# JTAG_Configuration.net
KiCad netlist of a schematic drawn in Altium Designer
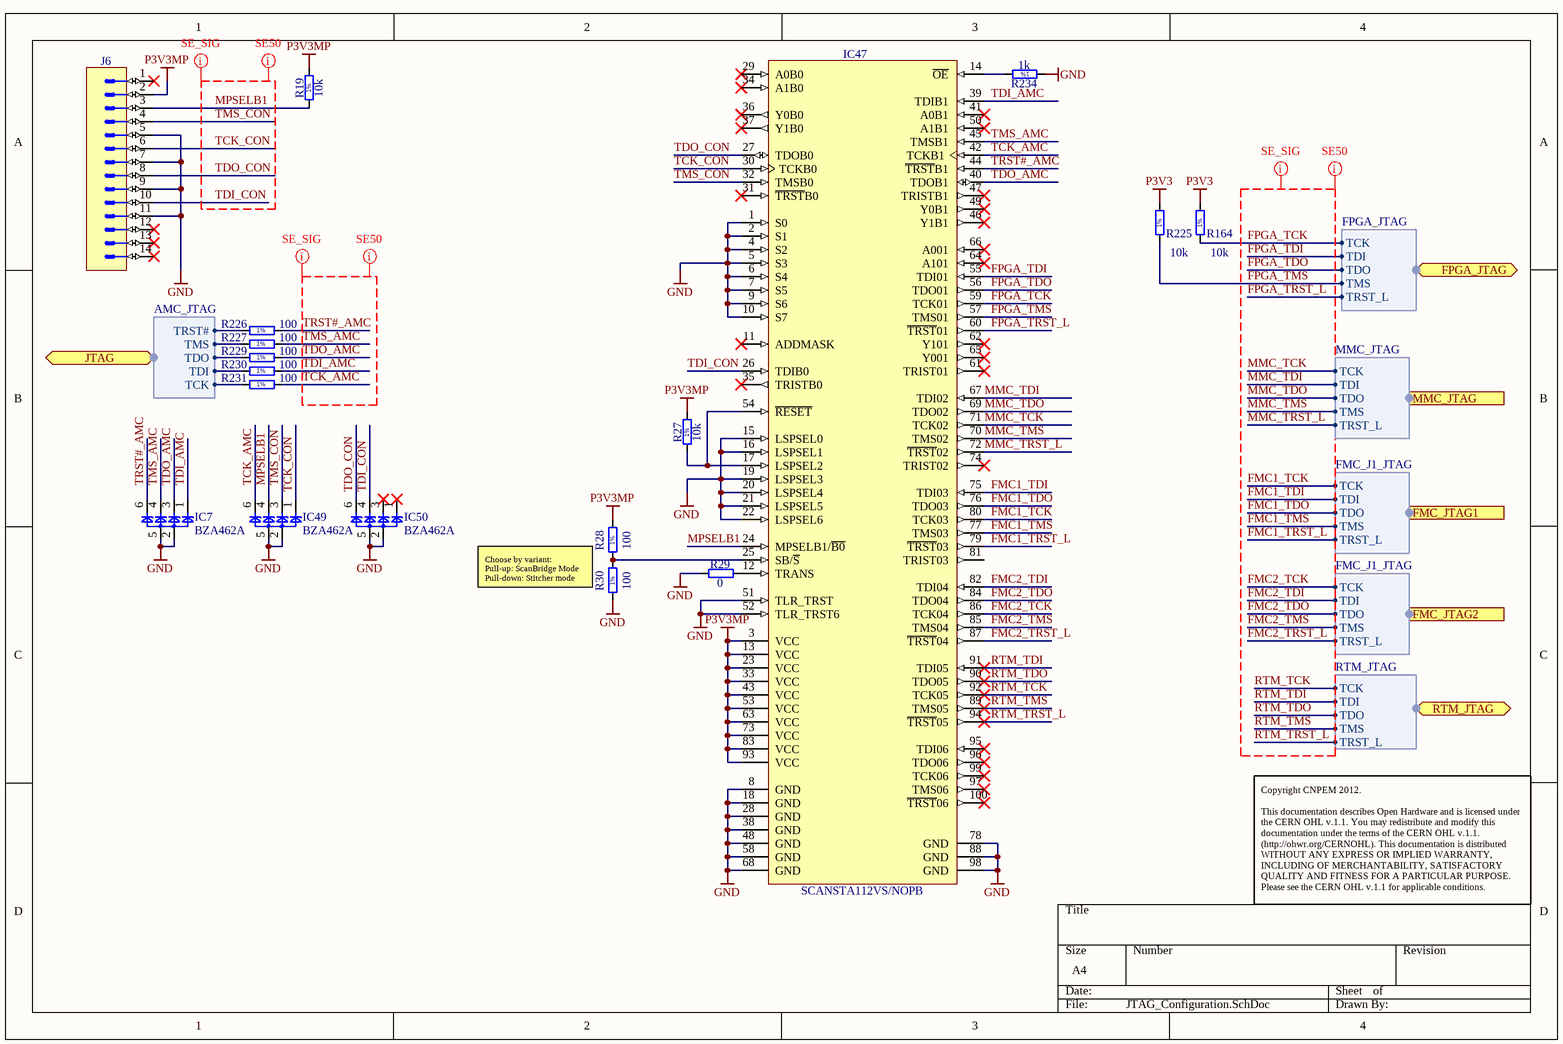
[diagram p0: JTAG_Configuration.SchDoc]

(export (version "E")
  (design (tool "Eeschema 10.0.6"))
  (components
    (comp (ref "IC7")
      (value "BZA462A")
      (footprint "SOT23-6")
      (description "Quadruple 4V ESD transient voltage suppressor")
      (libsource (lib "LIBRARY_SCH") (part "D_TVS_BZA462A"))
    )
    (comp (ref "IC47")
      (value "SCANSTA112VS/NOPB")
      (footprint "QFP50P1600X1600X120-100N")
      (description "7-Port Multidrop IEEE 1149.1 (JTAG) Multiplexer")
      (fields (field (name "MANUFACTURER") "TEXAS INSTRUMENTS") (field (name "AUTHOR") "CERN DEM JLC"))
      (libsource (lib "ICs And Semiconductors") (part "SCANSTA112VS"))
    )
    (comp (ref "IC49")
      (value "BZA462A")
      (footprint "SOT23-6")
      (description "Quadruple 4V ESD transient voltage suppressor")
      (libsource (lib "LIBRARY_SCH") (part "D_TVS_BZA462A"))
    )
    (comp (ref "IC50")
      (value "BZA462A")
      (footprint "SOT23-6")
      (description "Quadruple 4V ESD transient voltage suppressor")
      (libsource (lib "LIBRARY_SCH") (part "D_TVS_BZA462A"))
    )
    (comp (ref "J6")
      (value "Milli-Grid™")
      (footprint "MOLEX_87832-1420")
      (description "Connector 14 Male")
      (fields
        (field (name "PART NUMBER") "MOLEX_87832-1420")
        (field (name "MANUFACTURER") "MOLEX")
        (field (name "AUTHOR") "CERN DEM JLC")
      )
      (libsource (lib "Connectors") (part "Connector 14 Male"))
    )
    (comp (ref "R19")
      (value "10k")
      (footprint "RESC1608X55N")
      (description "Resistor - 1%")
      (fields
        (field (name "PART NUMBER") "R0603_10K_1%_0.1W_100PPM")
        (field (name "POWER") "0.1W")
        (field (name "AUTHOR") "CERN DEM JLC")
      )
      (libsource (lib "Resistors") (part "Resistor - 1%"))
    )
    (comp (ref "R27")
      (value "10k")
      (footprint "RESC1608X55N")
      (description "Resistor - 1%")
      (fields
        (field (name "PART NUMBER") "R0603_10K_1%_0.1W_100PPM")
        (field (name "POWER") "0.1W")
        (field (name "AUTHOR") "CERN DEM JLC")
      )
      (libsource (lib "Resistors") (part "Resistor - 1%"))
    )
    (comp (ref "R28")
      (value "100")
      (footprint "RESC1005X40N")
      (description "Resistor - 1%")
      (fields
        (field (name "PART NUMBER") "R0402_100R_1%_0.0625W_100PPM")
        (field (name "POWER") "0.0625W")
        (field (name "AUTHOR") "CERN DEM JLC")
      )
      (libsource (lib "Resistors") (part "Resistor - 1%"))
    )
    (comp (ref "R29")
      (value "0")
      (footprint "RESC1608X55N")
      (description "Resistor")
      (fields
        (field (name "PART NUMBER") "R0603_0R_JUMPER")
        (field (name "MANUFACTURER") "GENERIC")
        (field (name "AUTHOR") "CERN DEM JLC")
      )
      (libsource (lib "Resistors") (part "Resistor"))
    )
    (comp (ref "R30")
      (value "100")
      (footprint "RESC1005X40N")
      (description "Resistor - 1%")
      (fields
        (field (name "PART NUMBER") "R0402_100R_1%_0.0625W_100PPM")
        (field (name "POWER") "0.0625W")
        (field (name "AUTHOR") "CERN DEM JLC")
      )
      (libsource (lib "Resistors") (part "Resistor - 1%"))
    )
    (comp (ref "R164")
      (value "10k")
      (footprint "RESC1005X40N")
      (description "Resistor - 1%")
      (fields
        (field (name "PART NUMBER") "R0402_10K_1%_0.0625W_100PPM")
        (field (name "POWER") "0.0625W")
        (field (name "AUTHOR") "CERN DEM JLC")
      )
      (libsource (lib "Resistors") (part "Resistor - 1%"))
    )
    (comp (ref "R225")
      (value "10k")
      (footprint "RESC1005X40N")
      (description "Resistor - 1%")
      (fields
        (field (name "PART NUMBER") "R0402_10K_1%_0.0625W_100PPM")
        (field (name "POWER") "0.0625W")
        (field (name "AUTHOR") "CERN DEM JLC")
      )
      (libsource (lib "Resistors") (part "Resistor - 1%"))
    )
    (comp (ref "R226")
      (value "100")
      (footprint "RESC1005X40N")
      (description "Resistor - 1%")
      (fields
        (field (name "PART NUMBER") "R0402_100R_1%_0.0625W_100PPM")
        (field (name "POWER") "0.0625W")
        (field (name "AUTHOR") "CERN DEM JLC")
      )
      (libsource (lib "Resistors") (part "Resistor - 1%"))
    )
    (comp (ref "R227")
      (value "100")
      (footprint "RESC1005X40N")
      (description "Resistor - 1%")
      (fields
        (field (name "PART NUMBER") "R0402_100R_1%_0.0625W_100PPM")
        (field (name "POWER") "0.0625W")
        (field (name "AUTHOR") "CERN DEM JLC")
      )
      (libsource (lib "Resistors") (part "Resistor - 1%"))
    )
    (comp (ref "R229")
      (value "100")
      (footprint "RESC1005X40N")
      (description "Resistor - 1%")
      (fields
        (field (name "PART NUMBER") "R0402_100R_1%_0.0625W_100PPM")
        (field (name "POWER") "0.0625W")
        (field (name "AUTHOR") "CERN DEM JLC")
      )
      (libsource (lib "Resistors") (part "Resistor - 1%"))
    )
    (comp (ref "R230")
      (value "100")
      (footprint "RESC1005X40N")
      (description "Resistor - 1%")
      (fields
        (field (name "PART NUMBER") "R0402_100R_1%_0.0625W_100PPM")
        (field (name "POWER") "0.0625W")
        (field (name "AUTHOR") "CERN DEM JLC")
      )
      (libsource (lib "Resistors") (part "Resistor - 1%"))
    )
    (comp (ref "R231")
      (value "100")
      (footprint "RESC1005X40N")
      (description "Resistor - 1%")
      (fields
        (field (name "PART NUMBER") "R0402_100R_1%_0.0625W_100PPM")
        (field (name "POWER") "0.0625W")
        (field (name "AUTHOR") "CERN DEM JLC")
      )
      (libsource (lib "Resistors") (part "Resistor - 1%"))
    )
    (comp (ref "R234")
      (value "1k")
      (footprint "RESC1005X40N")
      (description "Resistor - 1%")
      (fields
        (field (name "PART NUMBER") "R0402_1K_1%_0.0625W_100PPM")
        (field (name "POWER") "0.0625W")
        (field (name "AUTHOR") "CERN DEM JLC")
      )
      (libsource (lib "Resistors") (part "Resistor - 1%"))
    )
  )
  (nets
    (net (code "6") (name "/FMC1_TCK") (class "Default")
      (node (ref "IC47") (pin "80") (pinfunction "TCK03_80") (pintype "output"))
    )
    (net (code "7") (name "/FMC1_TDI") (class "Default")
      (node (ref "IC47") (pin "75") (pinfunction "TDI03_75") (pintype "input"))
    )
    (net (code "8") (name "/FMC1_TDO") (class "Default")
      (node (ref "IC47") (pin "76") (pinfunction "TDO03_76") (pintype "output"))
    )
    (net (code "9") (name "/FMC1_TMS") (class "Default")
      (node (ref "IC47") (pin "77") (pinfunction "TMS03_77") (pintype "output"))
    )
    (net (code "10") (name "/FMC1_TRST_L") (class "Default")
      (node (ref "IC47") (pin "79") (pinfunction "~{TRST}03_79") (pintype "output"))
    )
    (net (code "11") (name "/FMC2_TCK") (class "Default")
      (node (ref "IC47") (pin "86") (pinfunction "TCK04_86") (pintype "output"))
    )
    (net (code "12") (name "/FMC2_TDI") (class "Default")
      (node (ref "IC47") (pin "82") (pinfunction "TDI04_82") (pintype "input"))
    )
    (net (code "13") (name "/FMC2_TDO") (class "Default")
      (node (ref "IC47") (pin "84") (pinfunction "TDO04_84") (pintype "output"))
    )
    (net (code "14") (name "/FMC2_TMS") (class "Default")
      (node (ref "IC47") (pin "85") (pinfunction "TMS04_85") (pintype "output"))
    )
    (net (code "15") (name "/FMC2_TRST_L") (class "Default")
      (node (ref "IC47") (pin "87") (pinfunction "~{TRST}04_87") (pintype "output"))
    )
    (net (code "16") (name "/FPGA_TCK") (class "Default")
      (node (ref "IC47") (pin "59") (pinfunction "TCK01_59") (pintype "output"))
      (node (ref "R164") (pin "1") (pinfunction "1_1") (pintype "passive"))
    )
    (net (code "17") (name "/FPGA_TDI") (class "Default")
      (node (ref "IC47") (pin "55") (pinfunction "TDI01_55") (pintype "input"))
    )
    (net (code "18") (name "/FPGA_TDO") (class "Default")
      (node (ref "IC47") (pin "56") (pinfunction "TDO01_56") (pintype "output"))
    )
    (net (code "19") (name "/FPGA_TMS") (class "Default")
      (node (ref "IC47") (pin "57") (pinfunction "TMS01_57") (pintype "output"))
      (node (ref "R225") (pin "1") (pinfunction "1_1") (pintype "passive"))
    )
    (net (code "20") (name "/FPGA_TRST_L") (class "Default")
      (node (ref "IC47") (pin "60") (pinfunction "~{TRST}01_60") (pintype "output"))
    )
    (net (code "21") (name "/MMC_TCK") (class "Default")
      (node (ref "IC47") (pin "71") (pinfunction "TCK02_71") (pintype "output"))
    )
    (net (code "22") (name "/MMC_TDI") (class "Default")
      (node (ref "IC47") (pin "67") (pinfunction "TDI02_67") (pintype "input"))
    )
    (net (code "23") (name "/MMC_TDO") (class "Default")
      (node (ref "IC47") (pin "69") (pinfunction "TDO02_69") (pintype "output"))
    )
    (net (code "24") (name "/MMC_TMS") (class "Default")
      (node (ref "IC47") (pin "70") (pinfunction "TMS02_70") (pintype "output"))
    )
    (net (code "25") (name "/MMC_TRST_L") (class "Default")
      (node (ref "IC47") (pin "72") (pinfunction "~{TRST}02_72") (pintype "output"))
    )
    (net (code "26") (name "/MPSELB1") (class "Default")
      (node (ref "IC47") (pin "24") (pinfunction "MPSELB1/~{B0}_24") (pintype "input"))
      (node (ref "IC49") (pin "4") (pinfunction "4_4") (pintype "passive"))
      (node (ref "J6") (pin "3") (pinfunction "3_3") (pintype "bidirectional"))
      (node (ref "R19") (pin "1") (pinfunction "1_1") (pintype "passive"))
    )
    (net (code "27") (name "/RTM_TCK") (class "Default")
      (node (ref "IC47") (pin "92") (pinfunction "TCK05_92") (pintype "output+no_connect"))
    )
    (net (code "28") (name "/RTM_TDI") (class "Default")
      (node (ref "IC47") (pin "91") (pinfunction "TDI05_91") (pintype "input"))
    )
    (net (code "29") (name "/RTM_TDO") (class "Default")
      (node (ref "IC47") (pin "90") (pinfunction "TDO05_90") (pintype "output"))
    )
    (net (code "30") (name "/RTM_TMS") (class "Default")
      (node (ref "IC47") (pin "89") (pinfunction "TMS05_89") (pintype "output"))
    )
    (net (code "31") (name "/RTM_TRST_L") (class "Default")
      (node (ref "IC47") (pin "94") (pinfunction "~{TRST}05_94") (pintype "output+no_connect"))
    )
    (net (code "32") (name "/TCK_AMC") (class "Default")
      (node (ref "IC47") (pin "42") (pinfunction "TCKB1_42") (pintype "input"))
      (node (ref "IC49") (pin "6") (pinfunction "6_6") (pintype "passive"))
      (node (ref "R231") (pin "2") (pinfunction "2_2") (pintype "passive"))
    )
    (net (code "33") (name "/TCK_CON") (class "Default")
      (node (ref "IC47") (pin "30") (pinfunction "TCKB0_30") (pintype "input"))
      (node (ref "IC49") (pin "1") (pinfunction "1_1") (pintype "passive"))
      (node (ref "J6") (pin "6") (pinfunction "6_6") (pintype "bidirectional"))
    )
    (net (code "34") (name "/TDI_AMC") (class "Default")
      (node (ref "IC47") (pin "39") (pinfunction "TDIB1_39") (pintype "input"))
      (node (ref "IC7") (pin "1") (pinfunction "1_1") (pintype "passive"))
      (node (ref "R230") (pin "2") (pinfunction "2_2") (pintype "passive"))
    )
    (net (code "35") (name "/TDI_CON") (class "Default")
      (node (ref "IC47") (pin "26") (pinfunction "TDIB0_26") (pintype "input"))
      (node (ref "IC50") (pin "4") (pinfunction "4_4") (pintype "passive"))
      (node (ref "J6") (pin "10") (pinfunction "10_10") (pintype "bidirectional"))
    )
    (net (code "36") (name "/TDO_AMC") (class "Default")
      (node (ref "IC47") (pin "40") (pinfunction "TDOB1_40") (pintype "bidirectional"))
      (node (ref "IC7") (pin "3") (pinfunction "3_3") (pintype "passive"))
      (node (ref "R229") (pin "2") (pinfunction "2_2") (pintype "passive"))
    )
    (net (code "37") (name "/TDO_CON") (class "Default")
      (node (ref "IC47") (pin "27") (pinfunction "TDOB0_27") (pintype "bidirectional"))
      (node (ref "IC50") (pin "6") (pinfunction "6_6") (pintype "passive"))
      (node (ref "J6") (pin "8") (pinfunction "8_8") (pintype "bidirectional"))
    )
    (net (code "38") (name "/TMS_AMC") (class "Default")
      (node (ref "IC47") (pin "45") (pinfunction "TMSB1_45") (pintype "input"))
      (node (ref "IC7") (pin "4") (pinfunction "4_4") (pintype "passive"))
      (node (ref "R227") (pin "2") (pinfunction "2_2") (pintype "passive"))
    )
    (net (code "39") (name "/TMS_CON") (class "Default")
      (node (ref "IC47") (pin "32") (pinfunction "TMSB0_32") (pintype "input"))
      (node (ref "IC49") (pin "3") (pinfunction "3_3") (pintype "passive"))
      (node (ref "J6") (pin "4") (pinfunction "4_4") (pintype "bidirectional"))
    )
    (net (code "40") (name "/TRST#") (class "Default")
      (node (ref "R226") (pin "1") (pinfunction "1_1") (pintype "passive"))
    )
    (net (code "41") (name "/TRST#_AMC") (class "Default")
      (node (ref "IC47") (pin "44") (pinfunction "~{TRST}B1_44") (pintype "input"))
      (node (ref "IC7") (pin "6") (pinfunction "6_6") (pintype "passive"))
      (node (ref "R226") (pin "2") (pinfunction "2_2") (pintype "passive"))
    )
    (net (code "47") (name "GND") (class "Default")
      (node (ref "IC47") (pin "1") (pinfunction "S0_1") (pintype "input"))
      (node (ref "IC47") (pin "10") (pinfunction "S7_10") (pintype "input"))
      (node (ref "IC47") (pin "15") (pinfunction "LSPSEL0_15") (pintype "input"))
      (node (ref "IC47") (pin "16") (pinfunction "LSPSEL1_16") (pintype "input"))
      (node (ref "IC47") (pin "18") (pinfunction "GND_18") (pintype "power_in"))
      (node (ref "IC47") (pin "19") (pinfunction "LSPSEL3_19") (pintype "input"))
      (node (ref "IC47") (pin "2") (pinfunction "S1_2") (pintype "input"))
      (node (ref "IC47") (pin "20") (pinfunction "LSPSEL4_20") (pintype "input"))
      (node (ref "IC47") (pin "21") (pinfunction "LSPSEL5_21") (pintype "input"))
      (node (ref "IC47") (pin "22") (pinfunction "LSPSEL6_22") (pintype "input"))
      (node (ref "IC47") (pin "28") (pinfunction "GND_28") (pintype "power_in"))
      (node (ref "IC47") (pin "38") (pinfunction "GND_38") (pintype "power_in"))
      (node (ref "IC47") (pin "4") (pinfunction "S2_4") (pintype "input"))
      (node (ref "IC47") (pin "48") (pinfunction "GND_48") (pintype "power_in"))
      (node (ref "IC47") (pin "5") (pinfunction "S3_5") (pintype "input"))
      (node (ref "IC47") (pin "51") (pinfunction "TLR_TRST_51") (pintype "input"))
      (node (ref "IC47") (pin "52") (pinfunction "TLR_TRST6_52") (pintype "input"))
      (node (ref "IC47") (pin "58") (pinfunction "GND_58") (pintype "power_in"))
      (node (ref "IC47") (pin "6") (pinfunction "S4_6") (pintype "input"))
      (node (ref "IC47") (pin "68") (pinfunction "GND_68") (pintype "power_in"))
      (node (ref "IC47") (pin "7") (pinfunction "S5_7") (pintype "input"))
      (node (ref "IC47") (pin "78") (pinfunction "GND_78") (pintype "power_in"))
      (node (ref "IC47") (pin "8") (pinfunction "GND_8") (pintype "power_in"))
      (node (ref "IC47") (pin "88") (pinfunction "GND_88") (pintype "power_in"))
      (node (ref "IC47") (pin "9") (pinfunction "S6_9") (pintype "input"))
      (node (ref "IC47") (pin "98") (pinfunction "GND_98") (pintype "power_in"))
      (node (ref "IC49") (pin "2") (pinfunction "2_2") (pintype "passive"))
      (node (ref "IC49") (pin "5") (pinfunction "5_5") (pintype "passive"))
      (node (ref "IC50") (pin "2") (pinfunction "2_2") (pintype "passive"))
      (node (ref "IC50") (pin "5") (pinfunction "5_5") (pintype "passive"))
      (node (ref "IC7") (pin "2") (pinfunction "2_2") (pintype "passive"))
      (node (ref "IC7") (pin "5") (pinfunction "5_5") (pintype "passive"))
      (node (ref "J6") (pin "11") (pinfunction "11_11") (pintype "bidirectional"))
      (node (ref "J6") (pin "5") (pinfunction "5_5") (pintype "bidirectional"))
      (node (ref "J6") (pin "7") (pinfunction "7_7") (pintype "bidirectional"))
      (node (ref "J6") (pin "9") (pinfunction "9_9") (pintype "bidirectional"))
      (node (ref "R234") (pin "1") (pinfunction "1_1") (pintype "passive"))
      (node (ref "R29") (pin "1") (pinfunction "1_1") (pintype "passive"))
      (node (ref "R30") (pin "1") (pinfunction "1_1") (pintype "passive"))
    )
    (net (code "48") (name "Net-(IC47-LSPSEL2)") (class "Default")
      (node (ref "IC47") (pin "17") (pinfunction "LSPSEL2_17") (pintype "input"))
      (node (ref "IC47") (pin "54") (pinfunction "~{RESET}_54") (pintype "input"))
      (node (ref "R27") (pin "1") (pinfunction "1_1") (pintype "passive"))
    )
    (net (code "49") (name "Net-(IC47-SB{slash}~{S})") (class "Default")
      (node (ref "IC47") (pin "25") (pinfunction "SB/~{S}_25") (pintype "input"))
      (node (ref "R28") (pin "1") (pinfunction "1_1") (pintype "passive"))
      (node (ref "R30") (pin "2") (pinfunction "2_2") (pintype "passive"))
    )
    (net (code "50") (name "Net-(IC47-TRANS)") (class "Default")
      (node (ref "IC47") (pin "12") (pinfunction "TRANS_12") (pintype "input"))
      (node (ref "R29") (pin "2") (pinfunction "2_2") (pintype "passive"))
    )
    (net (code "51") (name "Net-(IC47-~{OE})") (class "Default")
      (node (ref "IC47") (pin "14") (pinfunction "~{OE}_14") (pintype "input"))
      (node (ref "R234") (pin "2") (pinfunction "2_2") (pintype "passive"))
    )
    (net (code "52") (name "P3V3") (class "Default")
      (node (ref "R164") (pin "2") (pinfunction "2_2") (pintype "passive"))
      (node (ref "R225") (pin "2") (pinfunction "2_2") (pintype "passive"))
    )
    (net (code "53") (name "P3V3MP") (class "Default")
      (node (ref "IC47") (pin "13") (pinfunction "VCC_13") (pintype "power_in"))
      (node (ref "IC47") (pin "23") (pinfunction "VCC_23") (pintype "power_in"))
      (node (ref "IC47") (pin "3") (pinfunction "VCC_3") (pintype "power_in"))
      (node (ref "IC47") (pin "33") (pinfunction "VCC_33") (pintype "power_in"))
      (node (ref "IC47") (pin "43") (pinfunction "VCC_43") (pintype "power_in"))
      (node (ref "IC47") (pin "53") (pinfunction "VCC_53") (pintype "power_in"))
      (node (ref "IC47") (pin "63") (pinfunction "VCC_63") (pintype "power_in"))
      (node (ref "IC47") (pin "73") (pinfunction "VCC_73") (pintype "power_in"))
      (node (ref "IC47") (pin "83") (pinfunction "VCC_83") (pintype "power_in"))
      (node (ref "IC47") (pin "93") (pinfunction "VCC_93") (pintype "power_in"))
      (node (ref "J6") (pin "2") (pinfunction "2_2") (pintype "bidirectional"))
      (node (ref "R19") (pin "2") (pinfunction "2_2") (pintype "passive"))
      (node (ref "R27") (pin "2") (pinfunction "2_2") (pintype "passive"))
      (node (ref "R28") (pin "2") (pinfunction "2_2") (pintype "passive"))
    )
    (net (code "54") (name "unconnected-(IC47-A0B0-Pad29)") (class "Default")
      (node (ref "IC47") (pin "29") (pinfunction "A0B0_29") (pintype "input+no_connect"))
    )
    (net (code "55") (name "unconnected-(IC47-A0B1-Pad41)") (class "Default")
      (node (ref "IC47") (pin "41") (pinfunction "A0B1_41") (pintype "input+no_connect"))
    )
    (net (code "56") (name "unconnected-(IC47-A001-Pad66)") (class "Default")
      (node (ref "IC47") (pin "66") (pinfunction "A001_66") (pintype "input+no_connect"))
    )
    (net (code "57") (name "unconnected-(IC47-A1B0-Pad34)") (class "Default")
      (node (ref "IC47") (pin "34") (pinfunction "A1B0_34") (pintype "input+no_connect"))
    )
    (net (code "58") (name "unconnected-(IC47-A1B1-Pad50)") (class "Default")
      (node (ref "IC47") (pin "50") (pinfunction "A1B1_50") (pintype "input+no_connect"))
    )
    (net (code "59") (name "unconnected-(IC47-A101-Pad64)") (class "Default")
      (node (ref "IC47") (pin "64") (pinfunction "A101_64") (pintype "input+no_connect"))
    )
    (net (code "60") (name "unconnected-(IC47-ADDMASK-Pad11)") (class "Default")
      (node (ref "IC47") (pin "11") (pinfunction "ADDMASK_11") (pintype "input+no_connect"))
    )
    (net (code "61") (name "unconnected-(IC47-TCK06-Pad99)") (class "Default")
      (node (ref "IC47") (pin "99") (pinfunction "TCK06_99") (pintype "output+no_connect"))
    )
    (net (code "62") (name "unconnected-(IC47-TDI06-Pad95)") (class "Default")
      (node (ref "IC47") (pin "95") (pinfunction "TDI06_95") (pintype "input+no_connect"))
    )
    (net (code "63") (name "unconnected-(IC47-TDO06-Pad96)") (class "Default")
      (node (ref "IC47") (pin "96") (pinfunction "TDO06_96") (pintype "output+no_connect"))
    )
    (net (code "64") (name "unconnected-(IC47-TMS06-Pad97)") (class "Default")
      (node (ref "IC47") (pin "97") (pinfunction "TMS06_97") (pintype "output+no_connect"))
    )
    (net (code "65") (name "unconnected-(IC47-TRIST01-Pad61)") (class "Default")
      (node (ref "IC47") (pin "61") (pinfunction "TRIST01_61") (pintype "output+no_connect"))
    )
    (net (code "66") (name "unconnected-(IC47-TRIST02-Pad74)") (class "Default")
      (node (ref "IC47") (pin "74") (pinfunction "TRIST02_74") (pintype "output+no_connect"))
    )
    (net (code "67") (name "unconnected-(IC47-TRIST03-Pad81)") (class "Default")
      (node (ref "IC47") (pin "81") (pinfunction "TRIST03_81") (pintype "output"))
    )
    (net (code "68") (name "unconnected-(IC47-TRISTB0-Pad35)") (class "Default")
      (node (ref "IC47") (pin "35") (pinfunction "TRISTB0_35") (pintype "output+no_connect"))
    )
    (net (code "69") (name "unconnected-(IC47-TRISTB1-Pad47)") (class "Default")
      (node (ref "IC47") (pin "47") (pinfunction "TRISTB1_47") (pintype "output+no_connect"))
    )
    (net (code "70") (name "unconnected-(IC47-Y0B0-Pad36)") (class "Default")
      (node (ref "IC47") (pin "36") (pinfunction "Y0B0_36") (pintype "output+no_connect"))
    )
    (net (code "71") (name "unconnected-(IC47-Y0B1-Pad49)") (class "Default")
      (node (ref "IC47") (pin "49") (pinfunction "Y0B1_49") (pintype "output+no_connect"))
    )
    (net (code "72") (name "unconnected-(IC47-Y001-Pad65)") (class "Default")
      (node (ref "IC47") (pin "65") (pinfunction "Y001_65") (pintype "output+no_connect"))
    )
    (net (code "73") (name "unconnected-(IC47-Y1B0-Pad37)") (class "Default")
      (node (ref "IC47") (pin "37") (pinfunction "Y1B0_37") (pintype "output+no_connect"))
    )
    (net (code "74") (name "unconnected-(IC47-Y1B1-Pad46)") (class "Default")
      (node (ref "IC47") (pin "46") (pinfunction "Y1B1_46") (pintype "output+no_connect"))
    )
    (net (code "75") (name "unconnected-(IC47-Y101-Pad62)") (class "Default")
      (node (ref "IC47") (pin "62") (pinfunction "Y101_62") (pintype "output+no_connect"))
    )
    (net (code "76") (name "unconnected-(IC47-~{TRST}06-Pad100)") (class "Default")
      (node (ref "IC47") (pin "100") (pinfunction "~{TRST}06_100") (pintype "output+no_connect"))
    )
    (net (code "77") (name "unconnected-(IC47-~{TRST}B0-Pad31)") (class "Default")
      (node (ref "IC47") (pin "31") (pinfunction "~{TRST}B0_31") (pintype "input+no_connect"))
    )
    (net (code "78") (name "unconnected-(IC50-Pad1)") (class "Default")
      (node (ref "IC50") (pin "1") (pinfunction "1_1") (pintype "passive+no_connect"))
    )
    (net (code "79") (name "unconnected-(IC50-Pad3)") (class "Default")
      (node (ref "IC50") (pin "3") (pinfunction "3_3") (pintype "passive+no_connect"))
    )
    (net (code "80") (name "unconnected-(J6-Pad1)") (class "Default")
      (node (ref "J6") (pin "1") (pinfunction "1_1") (pintype "bidirectional+no_connect"))
    )
    (net (code "81") (name "unconnected-(J6-Pad12)") (class "Default")
      (node (ref "J6") (pin "12") (pinfunction "12_12") (pintype "bidirectional+no_connect"))
    )
    (net (code "82") (name "unconnected-(J6-Pad13)") (class "Default")
      (node (ref "J6") (pin "13") (pinfunction "13_13") (pintype "bidirectional+no_connect"))
    )
    (net (code "83") (name "unconnected-(J6-Pad14)") (class "Default")
      (node (ref "J6") (pin "14") (pinfunction "14_14") (pintype "bidirectional+no_connect"))
    )
    (net (code "84") (name "unconnected-(R227-Pad1)") (class "Default")
      (node (ref "R227") (pin "1") (pinfunction "1_1") (pintype "passive"))
    )
    (net (code "85") (name "unconnected-(R229-Pad1)") (class "Default")
      (node (ref "R229") (pin "1") (pinfunction "1_1") (pintype "passive"))
    )
    (net (code "86") (name "unconnected-(R230-Pad1)") (class "Default")
      (node (ref "R230") (pin "1") (pinfunction "1_1") (pintype "passive"))
    )
    (net (code "87") (name "unconnected-(R231-Pad1)") (class "Default")
      (node (ref "R231") (pin "1") (pinfunction "1_1") (pintype "passive"))
    )
  )
)
